# EXP.net
KiCad netlist of a schematic drawn in Altium Designer
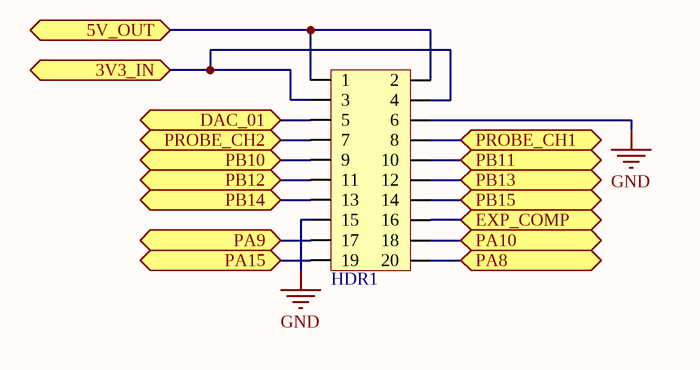
[diagram p0: EXP.SchDoc]

(export (version "E")
  (design (tool "Eeschema 10.0.6"))
  (components
    (comp (ref "HDR1")
      (value "HDR2x10_2.54")
      (footprint "HDR2X10_2.54_180HF")
      (description "Header")
      (libsource (lib "SCH_ConnectorHDR") (part "HDR2x10_2.54"))
    )
  )
  (nets
    (net (code "1") (name "/3V3_IN") (class "Default")
      (node (ref "HDR1") (pin "3") (pinfunction "3_3") (pintype "passive"))
      (node (ref "HDR1") (pin "4") (pinfunction "4_4") (pintype "passive"))
    )
    (net (code "2") (name "/5V_OUT") (class "Default")
      (node (ref "HDR1") (pin "1") (pinfunction "1_1") (pintype "passive"))
      (node (ref "HDR1") (pin "2") (pinfunction "2_2") (pintype "passive"))
    )
    (net (code "3") (name "/DAC_01") (class "Default")
      (node (ref "HDR1") (pin "5") (pinfunction "5_5") (pintype "passive"))
    )
    (net (code "4") (name "/EXP_COMP") (class "Default")
      (node (ref "HDR1") (pin "16") (pinfunction "16_16") (pintype "passive"))
    )
    (net (code "5") (name "/PA8") (class "Default")
      (node (ref "HDR1") (pin "20") (pinfunction "20_20") (pintype "passive"))
    )
    (net (code "6") (name "/PA9") (class "Default")
      (node (ref "HDR1") (pin "17") (pinfunction "17_17") (pintype "passive"))
    )
    (net (code "7") (name "/PA10") (class "Default")
      (node (ref "HDR1") (pin "18") (pinfunction "18_18") (pintype "passive"))
    )
    (net (code "8") (name "/PA15") (class "Default")
      (node (ref "HDR1") (pin "19") (pinfunction "19_19") (pintype "passive"))
    )
    (net (code "9") (name "/PB10") (class "Default")
      (node (ref "HDR1") (pin "9") (pinfunction "9_9") (pintype "passive"))
    )
    (net (code "10") (name "/PB11") (class "Default")
      (node (ref "HDR1") (pin "10") (pinfunction "10_10") (pintype "passive"))
    )
    (net (code "11") (name "/PB12") (class "Default")
      (node (ref "HDR1") (pin "11") (pinfunction "11_11") (pintype "passive"))
    )
    (net (code "12") (name "/PB13") (class "Default")
      (node (ref "HDR1") (pin "12") (pinfunction "12_12") (pintype "passive"))
    )
    (net (code "13") (name "/PB14") (class "Default")
      (node (ref "HDR1") (pin "13") (pinfunction "13_13") (pintype "passive"))
    )
    (net (code "14") (name "/PB15") (class "Default")
      (node (ref "HDR1") (pin "14") (pinfunction "14_14") (pintype "passive"))
    )
    (net (code "15") (name "/PROBE_CH1") (class "Default")
      (node (ref "HDR1") (pin "8") (pinfunction "8_8") (pintype "passive"))
    )
    (net (code "16") (name "/PROBE_CH2") (class "Default")
      (node (ref "HDR1") (pin "7") (pinfunction "7_7") (pintype "passive"))
    )
    (net (code "17") (name "GND") (class "Default")
      (node (ref "HDR1") (pin "15") (pinfunction "15_15") (pintype "passive"))
      (node (ref "HDR1") (pin "6") (pinfunction "6_6") (pintype "passive"))
    )
  )
)
